# CATZILLA.net
KiCad netlist of a schematic drawn in Altium Designer
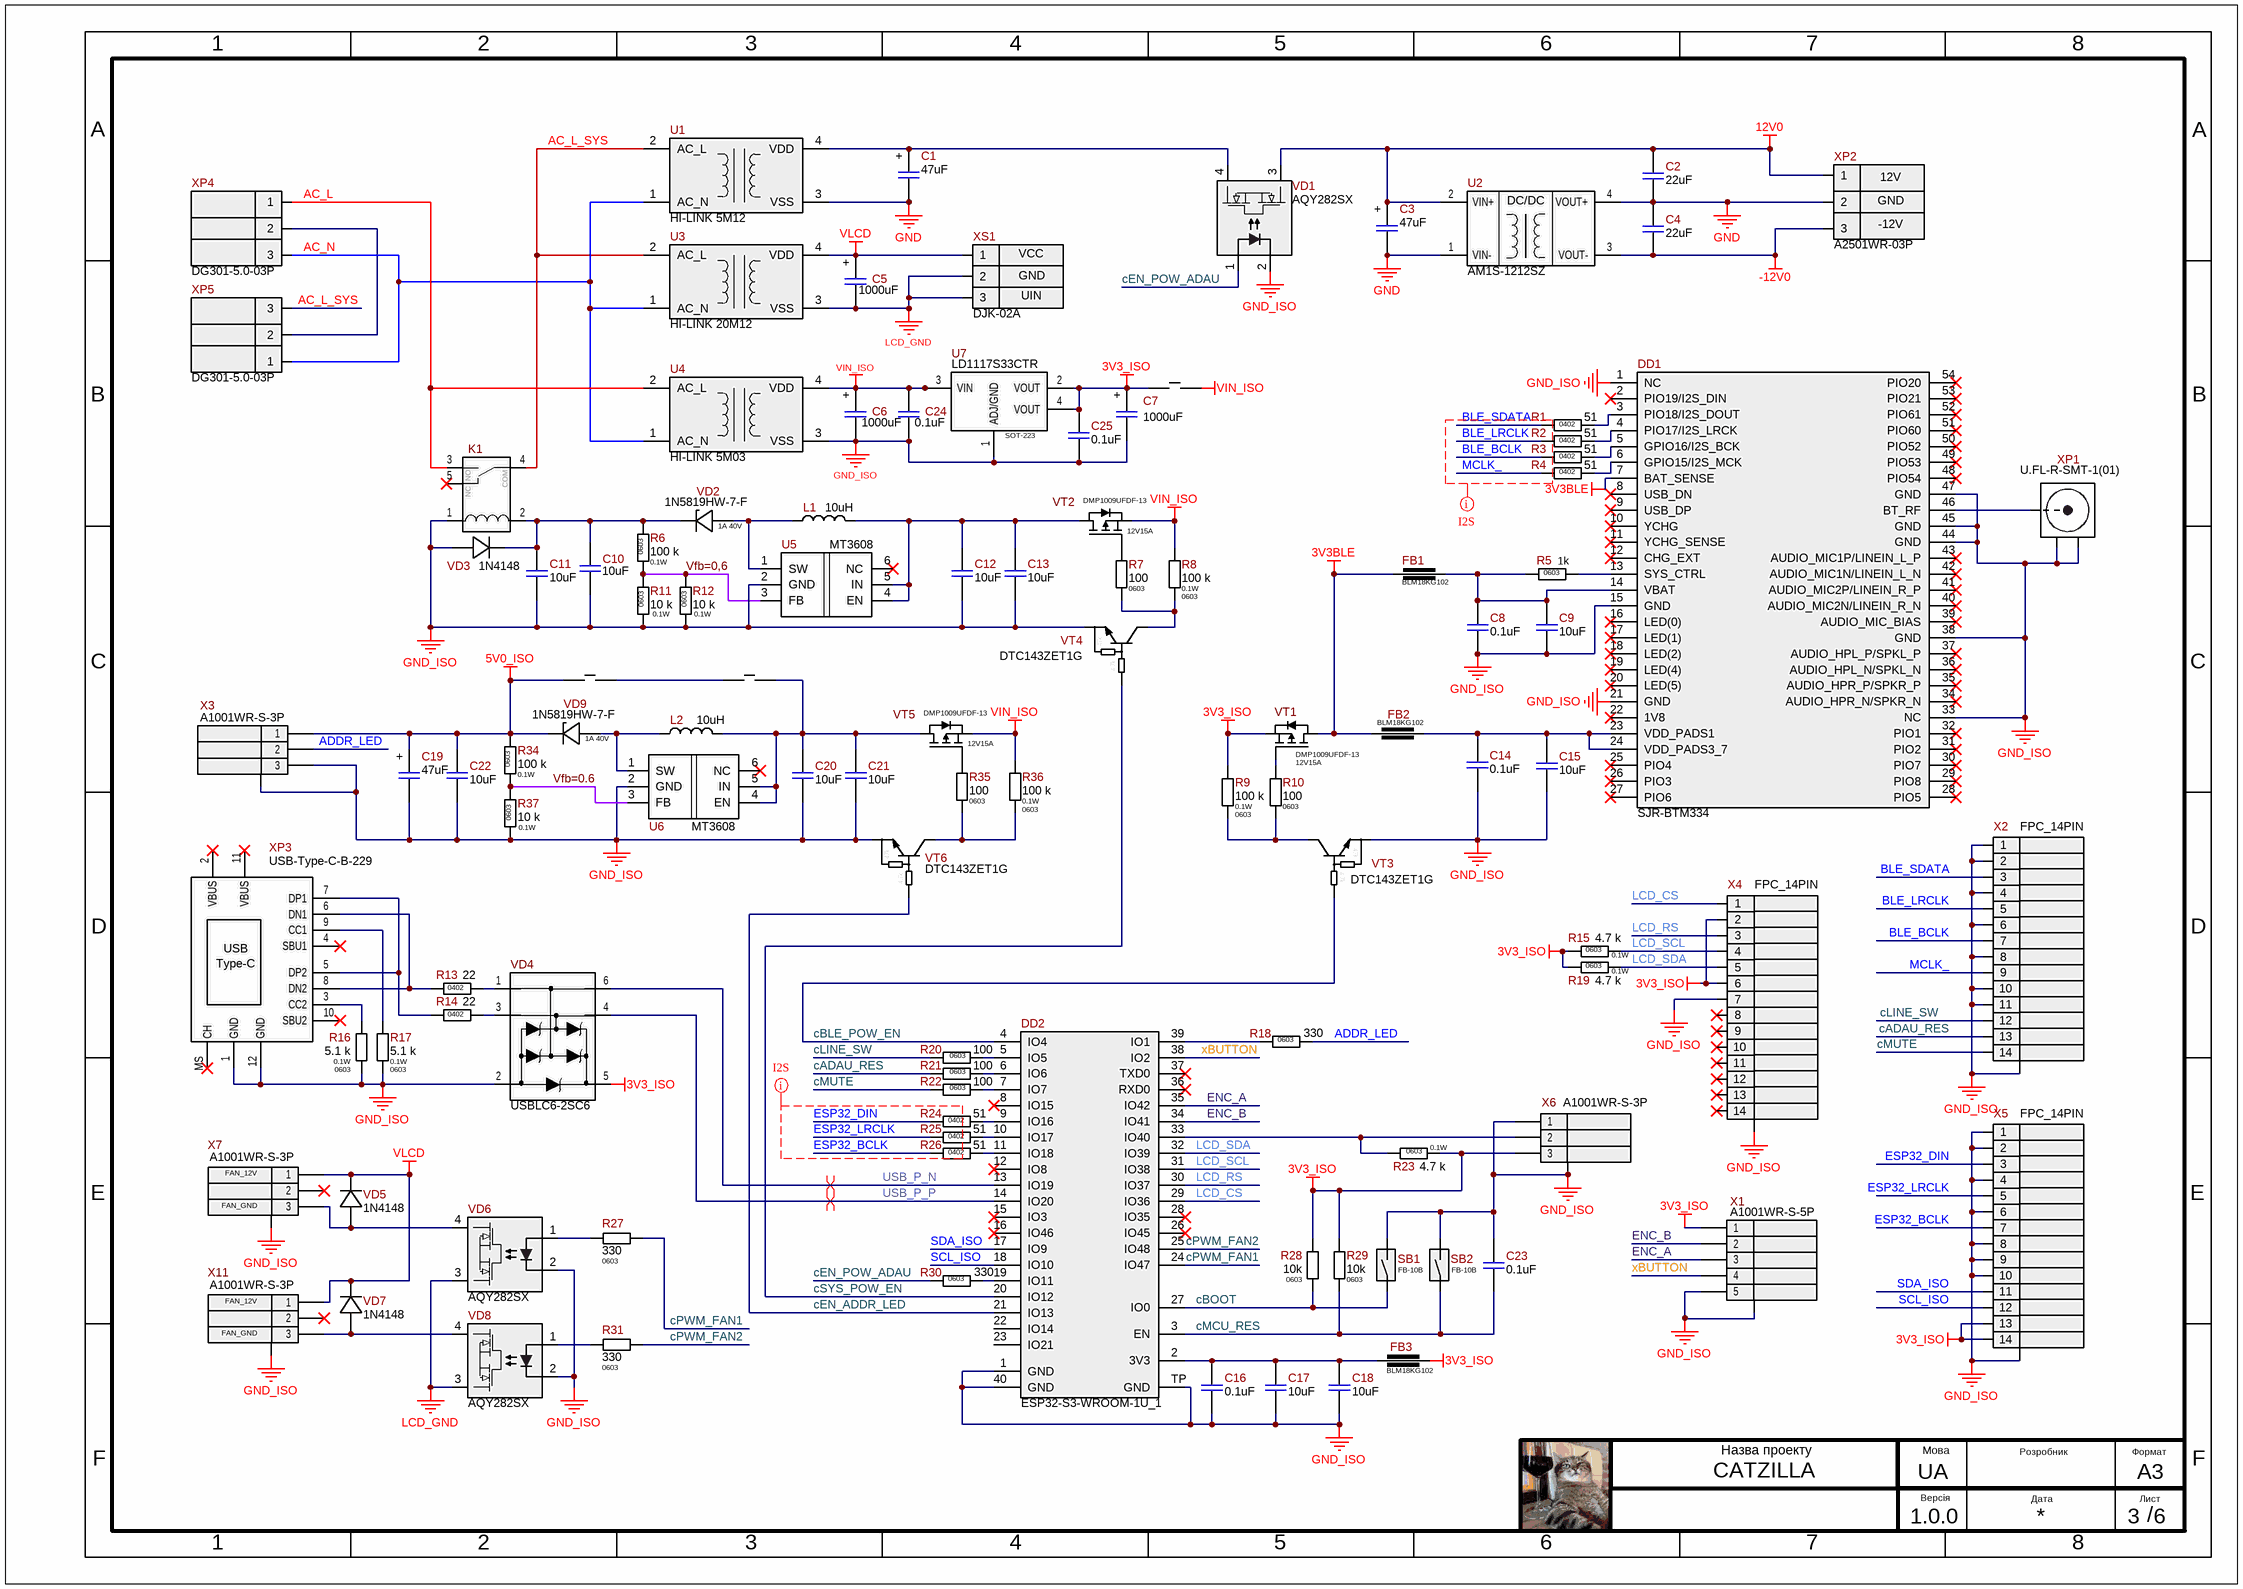
[diagram p0: CATZILLA.SchDoc]

(export (version "E")
  (design (tool "Eeschema 10.0.6"))
  (components
    (comp (ref "C1")
      (value "47uF")
      (footprint "CAP 6.3x6")
      (description "CAP ALUM POLY 47UF 10% 25V SMD")
      (fields (field (name "PART NUMBER") "47uF  25V 6.3х5.3") (field (name "TOLERANCE") "±10%"))
      (libsource (lib "Database") (part "Capacitor_Electrolytic"))
    )
    (comp (ref "C2")
      (value "22uF")
      (footprint "C1206(3216)")
      (description "CAP CER 22UF 25V X5R 1206")
      (fields (field (name "PART NUMBER") "22uF  25V С1206") (field (name "TOLERANCE") "±10%"))
      (libsource (lib "Database") (part "Capacitor_Ceramic"))
    )
    (comp (ref "C3")
      (value "47uF")
      (footprint "CAP 6.3x6")
      (description "CAP ALUM POLY 47UF 10% 25V SMD")
      (fields (field (name "PART NUMBER") "47uF  25V 6.3х5.3") (field (name "TOLERANCE") "±10%"))
      (libsource (lib "Database") (part "Capacitor_Electrolytic"))
    )
    (comp (ref "C4")
      (value "22uF")
      (footprint "C1206(3216)")
      (description "CAP CER 22UF 25V X5R 1206")
      (fields (field (name "PART NUMBER") "22uF  25V С1206") (field (name "TOLERANCE") "±10%"))
      (libsource (lib "Database") (part "Capacitor_Ceramic"))
    )
    (comp (ref "C5")
      (value "1000uF")
      (footprint "CAP 10x16")
      (description "1000uF 20% 16V EHR 10x16mm")
      (fields (field (name "PART NUMBER") "1000uF  16V 10x16(EHR)") (field (name "TOLERANCE") "±20%"))
      (libsource (lib "Database") (part "Capacitor_Electrolytic"))
    )
    (comp (ref "C6")
      (value "1000uF")
      (footprint "CAP-AE-830x1000H50_HI")
      (description "1000uF 6.3V Size E D8x10.5mm")
      (fields (field (name "PART NUMBER") "1000uF  6.3V Size E D8x10.5mm") (field (name "TOLERANCE") "10%"))
      (libsource (lib "Database") (part "Capacitor_Electrolytic"))
    )
    (comp (ref "C7")
      (value "1000uF")
      (footprint "CAP-AE-830x1000H50_HI")
      (description "1000uF 6.3V Size E D8x10.5mm")
      (fields (field (name "PART NUMBER") "1000uF  6.3V Size E D8x10.5mm") (field (name "TOLERANCE") "10%"))
      (libsource (lib "Database") (part "Capacitor_Electrolytic"))
    )
    (comp (ref "C8")
      (value "0.1uF")
      (footprint "C0603(1608)")
      (description "CAP CER 0.1UF 50V X7R 0603")
      (fields (field (name "PART NUMBER") "0.1uF  50V C0603") (field (name "TOLERANCE") "±10%"))
      (libsource (lib "Database") (part "Capacitor_Ceramic"))
    )
    (comp (ref "C9")
      (value "10uF")
      (footprint "C0603(1608)")
      (description "CAP CER 10UF 35V X5R 0603")
      (fields (field (name "PART NUMBER") "10uF  35V C0603") (field (name "TOLERANCE") "±20%"))
      (libsource (lib "Database") (part "Capacitor_Ceramic"))
    )
    (comp (ref "C10")
      (value "10uF")
      (footprint "C0805(2012)")
      (description "CAP CER 10UF 16V X6S 0805")
      (fields (field (name "PART NUMBER") "10uF  16V C0805") (field (name "TOLERANCE") "±10%"))
      (libsource (lib "Database") (part "Capacitor_Ceramic"))
    )
    (comp (ref "C11")
      (value "10uF")
      (footprint "C0805(2012)")
      (description "CAP CER 10UF 16V X6S 0805")
      (fields (field (name "PART NUMBER") "10uF  16V C0805") (field (name "TOLERANCE") "±10%"))
      (libsource (lib "Database") (part "Capacitor_Ceramic"))
    )
    (comp (ref "C12")
      (value "10uF")
      (footprint "C0805(2012)")
      (description "CAP CER 10UF 16V X6S 0805")
      (fields (field (name "PART NUMBER") "10uF  16V C0805") (field (name "TOLERANCE") "±10%"))
      (libsource (lib "Database") (part "Capacitor_Ceramic"))
    )
    (comp (ref "C13")
      (value "10uF")
      (footprint "C0805(2012)")
      (description "CAP CER 10UF 16V X6S 0805")
      (fields (field (name "PART NUMBER") "10uF  16V C0805") (field (name "TOLERANCE") "±10%"))
      (libsource (lib "Database") (part "Capacitor_Ceramic"))
    )
    (comp (ref "C14")
      (value "0.1uF")
      (footprint "C0603(1608)")
      (description "CAP CER 0.1UF 50V X7R 0603")
      (fields (field (name "PART NUMBER") "0.1uF  50V C0603") (field (name "TOLERANCE") "±10%"))
      (libsource (lib "Database") (part "Capacitor_Ceramic"))
    )
    (comp (ref "C15")
      (value "10uF")
      (footprint "C0603(1608)")
      (description "CAP CER 10UF 35V X5R 0603")
      (fields (field (name "PART NUMBER") "10uF  35V C0603") (field (name "TOLERANCE") "±20%"))
      (libsource (lib "Database") (part "Capacitor_Ceramic"))
    )
    (comp (ref "C16")
      (value "0.1uF")
      (footprint "C0603(1608)")
      (description "CAP CER 0.1UF 50V X7R 0603")
      (fields (field (name "PART NUMBER") "0.1uF  50V C0603") (field (name "TOLERANCE") "±10%"))
      (libsource (lib "Database") (part "Capacitor_Ceramic"))
    )
    (comp (ref "C17")
      (value "10uF")
      (footprint "C0603(1608)")
      (description "CAP CER 10UF 35V X5R 0603")
      (fields (field (name "PART NUMBER") "10uF  35V C0603") (field (name "TOLERANCE") "±20%"))
      (libsource (lib "Database") (part "Capacitor_Ceramic"))
    )
    (comp (ref "C18")
      (value "10uF")
      (footprint "C0603(1608)")
      (description "CAP CER 10UF 35V X5R 0603")
      (fields (field (name "PART NUMBER") "10uF  35V C0603") (field (name "TOLERANCE") "±20%"))
      (libsource (lib "Database") (part "Capacitor_Ceramic"))
    )
    (comp (ref "C19")
      (value "47uF")
      (footprint "CAP 6.3x6")
      (description "CAP ALUM POLY 47UF 10% 25V SMD")
      (fields (field (name "PART NUMBER") "47uF  25V 6.3х5.3") (field (name "TOLERANCE") "±10%"))
      (libsource (lib "Database") (part "Capacitor_Electrolytic"))
    )
    (comp (ref "C20")
      (value "10uF")
      (footprint "C0805(2012)")
      (description "CAP CER 10UF 16V X6S 0805")
      (fields (field (name "PART NUMBER") "10uF  16V C0805") (field (name "TOLERANCE") "±10%"))
      (libsource (lib "Database") (part "Capacitor_Ceramic"))
    )
    (comp (ref "C21")
      (value "10uF")
      (footprint "C0805(2012)")
      (description "CAP CER 10UF 16V X6S 0805")
      (fields (field (name "PART NUMBER") "10uF  16V C0805") (field (name "TOLERANCE") "±10%"))
      (libsource (lib "Database") (part "Capacitor_Ceramic"))
    )
    (comp (ref "C22")
      (value "10uF")
      (footprint "C0805(2012)")
      (description "CAP CER 10UF 16V X6S 0805")
      (fields (field (name "PART NUMBER") "10uF  16V C0805") (field (name "TOLERANCE") "±10%"))
      (libsource (lib "Database") (part "Capacitor_Ceramic"))
    )
    (comp (ref "C23")
      (value "0.1uF")
      (footprint "C0603(1608)")
      (description "CAP CER 0.1UF 50V X7R 0603")
      (fields (field (name "PART NUMBER") "0.1uF  50V C0603") (field (name "TOLERANCE") "±10%"))
      (libsource (lib "Database") (part "Capacitor_Ceramic"))
    )
    (comp (ref "C24")
      (value "0.1uF")
      (footprint "C0603(1608)")
      (description "CAP CER 0.1UF 50V X7R 0603")
      (fields (field (name "PART NUMBER") "0.1uF  50V C0603") (field (name "TOLERANCE") "±10%"))
      (libsource (lib "Database") (part "Capacitor_Ceramic"))
    )
    (comp (ref "C25")
      (value "0.1uF")
      (footprint "C0603(1608)")
      (description "CAP CER 0.1UF 50V X7R 0603")
      (fields (field (name "PART NUMBER") "0.1uF  50V C0603") (field (name "TOLERANCE") "±10%"))
      (libsource (lib "Database") (part "Capacitor_Ceramic"))
    )
    (comp (ref "DD1")
      (value "SJR-BTM334")
      (footprint "BTM334")
      (description "Bluetooth 5.1 audio module, QCC3034 chipset")
      (libsource (lib "Database") (part "BTM334"))
    )
    (comp (ref "DD2")
      (value "ESP32-S3-WROOM-1U_1")
      (footprint "ESP32-S3-WROOM-1U")
      (description "ESP32-S3-WROOM-1U-N16R8")
      (libsource (lib "Database") (part "ESP32-S3-WROOM-1U-1N16R2"))
    )
    (comp (ref "FB1")
      (value "BLM18KG102")
      (footprint "BLM18(0603)")
      (description "FERRITE BEAD 1 KOHM 0603 1LN")
      (fields
        (field (name "TOLERANCE") "±25%")
        (field (name "MANUFACTURER") "Murata Electronics North America")
      )
      (libsource (lib "Database") (part "FB"))
    )
    (comp (ref "FB2")
      (value "BLM18KG102")
      (footprint "BLM18(0603)")
      (description "FERRITE BEAD 1 KOHM 0603 1LN")
      (fields
        (field (name "TOLERANCE") "±25%")
        (field (name "MANUFACTURER") "Murata Electronics North America")
      )
      (libsource (lib "Database") (part "FB"))
    )
    (comp (ref "FB3")
      (value "BLM18KG102")
      (footprint "BLM18(0603)")
      (description "FERRITE BEAD 1 KOHM 0603 1LN")
      (fields
        (field (name "TOLERANCE") "±25%")
        (field (name "MANUFACTURER") "Murata Electronics North America")
      )
      (libsource (lib "Database") (part "FB"))
    )
    (comp (ref "K1")
      (value "LEG-12")
      (footprint "Relay10A")
      (description "General Purpose Relay, 1 Form C (1PDT), 12VDC 400Ohm Coil, 120VAC/24VDC @ 10A, 240VAC Max")
      (libsource (lib "Database") (part "RELAY10A"))
    )
    (comp (ref "L1")
      (value "10uH")
      (footprint "WE-LQS SMD 4018")
      (description "FIXED IND 10UH 1A 66 MOHM SMD")
      (fields (field (name "PART NUMBER") "NRS4018T3R3") (field (name "TOLERANCE") "±20"))
      (libsource (lib "Database") (part "INDUCTORS"))
    )
    (comp (ref "L2")
      (value "10uH")
      (footprint "WE-LQS SMD 4018")
      (description "FIXED IND 10UH 1A 66 MOHM SMD")
      (fields (field (name "PART NUMBER") "NRS4018T3R3") (field (name "TOLERANCE") "±20"))
      (libsource (lib "Database") (part "INDUCTORS"))
    )
    (comp (ref "R1")
      (value "51")
      (footprint "R0402")
      (description "RES SMD 51 OHM  ±1% 1/16W 0402")
      (fields
        (field (name "PACKAGE/CASE") "0402")
        (field (name "PART NUMBER") "51  R0402")
        (field (name "TOLERANCE") "±1%")
      )
      (libsource (lib "Database") (part "R0402"))
    )
    (comp (ref "R2")
      (value "51")
      (footprint "R0402")
      (description "RES SMD 51 OHM  ±1% 1/16W 0402")
      (fields
        (field (name "PACKAGE/CASE") "0402")
        (field (name "PART NUMBER") "51  R0402")
        (field (name "TOLERANCE") "±1%")
      )
      (libsource (lib "Database") (part "R0402"))
    )
    (comp (ref "R3")
      (value "51")
      (footprint "R0402")
      (description "RES SMD 51 OHM  ±1% 1/16W 0402")
      (fields
        (field (name "PACKAGE/CASE") "0402")
        (field (name "PART NUMBER") "51  R0402")
        (field (name "TOLERANCE") "±1%")
      )
      (libsource (lib "Database") (part "R0402"))
    )
    (comp (ref "R4")
      (value "51")
      (footprint "R0402")
      (description "RES SMD 51 OHM  ±1% 1/16W 0402")
      (fields
        (field (name "PACKAGE/CASE") "0402")
        (field (name "PART NUMBER") "51  R0402")
        (field (name "TOLERANCE") "±1%")
      )
      (libsource (lib "Database") (part "R0402"))
    )
    (comp (ref "R5")
      (value "1k")
      (footprint "R0603")
      (description "RES SMD 10 k OHM  ±1% 1/10W 0603")
      (fields
        (field (name "PACKAGE/CASE") "0603")
        (field (name "PART NUMBER") "10 k  R0603")
        (field (name "TOLERANCE") "±1%")
      )
      (libsource (lib "Database") (part "R0603"))
    )
    (comp (ref "R6")
      (value "100 k")
      (footprint "R0603")
      (description "RES SMD 100 k OHM  ±1% 1/10W 0603")
      (fields
        (field (name "POWER RATING") "0.1W")
        (field (name "PACKAGE/CASE") "0603")
        (field (name "PART NUMBER") "100 k  R0603")
        (field (name "TOLERANCE") "±1%")
      )
      (libsource (lib "Database") (part "R0603"))
    )
    (comp (ref "R7")
      (value "100")
      (footprint "R0603")
      (description "RES SMD 100 OHM  ±1% 1/10W 0603")
      (fields
        (field (name "PACKAGE/CASE") "0603")
        (field (name "PART NUMBER") "100  R0603")
        (field (name "TOLERANCE") "±1%")
      )
      (libsource (lib "Database") (part "R0603"))
    )
    (comp (ref "R8")
      (value "100 k")
      (footprint "R0603")
      (description "RES SMD 100 k OHM  ±1% 1/10W 0603")
      (fields
        (field (name "POWER RATING") "0.1W")
        (field (name "PACKAGE/CASE") "0603")
        (field (name "PART NUMBER") "100 k  R0603")
        (field (name "TOLERANCE") "±1%")
      )
      (libsource (lib "Database") (part "R0603"))
    )
    (comp (ref "R9")
      (value "100 k")
      (footprint "R0603")
      (description "RES SMD 100 k OHM  ±1% 1/10W 0603")
      (fields
        (field (name "POWER RATING") "0.1W")
        (field (name "PACKAGE/CASE") "0603")
        (field (name "PART NUMBER") "100 k  R0603")
        (field (name "TOLERANCE") "±1%")
      )
      (libsource (lib "Database") (part "R0603"))
    )
    (comp (ref "R10")
      (value "100")
      (footprint "R0603")
      (description "RES SMD 100 OHM  ±1% 1/10W 0603")
      (fields
        (field (name "PACKAGE/CASE") "0603")
        (field (name "PART NUMBER") "100  R0603")
        (field (name "TOLERANCE") "±1%")
      )
      (libsource (lib "Database") (part "R0603"))
    )
    (comp (ref "R11")
      (value "10 k")
      (footprint "R0603")
      (description "RES SMD 10 k OHM  ±1% 1/10W 0603")
      (fields
        (field (name "PACKAGE/CASE") "0603")
        (field (name "POWER RATING") "0.1W")
        (field (name "PART NUMBER") "10 k  R0603")
        (field (name "TOLERANCE") "±1%")
      )
      (libsource (lib "Database") (part "R0603"))
    )
    (comp (ref "R12")
      (value "10 k")
      (footprint "R0603")
      (description "RES SMD 10 k OHM  ±1% 1/10W 0603")
      (fields
        (field (name "PACKAGE/CASE") "0603")
        (field (name "POWER RATING") "0.1W")
        (field (name "PART NUMBER") "10 k  R0603")
        (field (name "TOLERANCE") "±1%")
      )
      (libsource (lib "Database") (part "R0603"))
    )
    (comp (ref "R13")
      (value "22")
      (footprint "R0402")
      (description "RES SMD 22 OHM  ±1% 1/16W 0402")
      (fields
        (field (name "PACKAGE/CASE") "0402")
        (field (name "PART NUMBER") "22  R0402")
        (field (name "TOLERANCE") "±1%")
      )
      (libsource (lib "Database") (part "R0402"))
    )
    (comp (ref "R14")
      (value "22")
      (footprint "R0402")
      (description "RES SMD 22 OHM  ±1% 1/16W 0402")
      (fields
        (field (name "PACKAGE/CASE") "0402")
        (field (name "PART NUMBER") "22  R0402")
        (field (name "TOLERANCE") "±1%")
      )
      (libsource (lib "Database") (part "R0402"))
    )
    (comp (ref "R15")
      (value "4.7 k")
      (footprint "R0603")
      (description "RES SMD 4.7 k OHM  ±1% 1/10W 0603")
      (fields
        (field (name "POWER RATING") "0.1W")
        (field (name "PACKAGE/CASE") "0603")
        (field (name "PART NUMBER") "4.7 k  R0603")
        (field (name "TOLERANCE") "±1%")
      )
      (libsource (lib "Database") (part "R0603"))
    )
    (comp (ref "R16")
      (value "5.1 k")
      (footprint "R0603")
      (description "RES SMD 5.1 k OHM  ±1% 1/10W 0603")
      (fields
        (field (name "POWER RATING") "0.1W")
        (field (name "PACKAGE/CASE") "0603")
        (field (name "PART NUMBER") "5.1 k  R0603")
        (field (name "TOLERANCE") "±1%")
      )
      (libsource (lib "Database") (part "R0603"))
    )
    (comp (ref "R17")
      (value "5.1 k")
      (footprint "R0603")
      (description "RES SMD 5.1 k OHM  ±1% 1/10W 0603")
      (fields
        (field (name "POWER RATING") "0.1W")
        (field (name "PACKAGE/CASE") "0603")
        (field (name "PART NUMBER") "5.1 k  R0603")
        (field (name "TOLERANCE") "±1%")
      )
      (libsource (lib "Database") (part "R0603"))
    )
    (comp (ref "R18")
      (value "330")
      (footprint "R0603")
      (description "RES SMD 330 OHM  ±1% 1/10W 0603")
      (fields
        (field (name "PACKAGE/CASE") "0603")
        (field (name "PART NUMBER") "330  R0603")
        (field (name "TOLERANCE") "±1%")
      )
      (libsource (lib "Database") (part "R0603"))
    )
    (comp (ref "R19")
      (value "4.7 k")
      (footprint "R0603")
      (description "RES SMD 4.7 k OHM  ±1% 1/10W 0603")
      (fields
        (field (name "POWER RATING") "0.1W")
        (field (name "PACKAGE/CASE") "0603")
        (field (name "PART NUMBER") "4.7 k  R0603")
        (field (name "TOLERANCE") "±1%")
      )
      (libsource (lib "Database") (part "R0603"))
    )
    (comp (ref "R20")
      (value "100")
      (footprint "R0603")
      (description "RES SMD 100 OHM  ±1% 1/10W 0603")
      (fields
        (field (name "PACKAGE/CASE") "0603")
        (field (name "PART NUMBER") "100  R0603")
        (field (name "TOLERANCE") "±1%")
      )
      (libsource (lib "Database") (part "R0603"))
    )
    (comp (ref "R21")
      (value "100")
      (footprint "R0603")
      (description "RES SMD 100 OHM  ±1% 1/10W 0603")
      (fields
        (field (name "PACKAGE/CASE") "0603")
        (field (name "PART NUMBER") "100  R0603")
        (field (name "TOLERANCE") "±1%")
      )
      (libsource (lib "Database") (part "R0603"))
    )
    (comp (ref "R22")
      (value "100")
      (footprint "R0603")
      (description "RES SMD 100 OHM  ±1% 1/10W 0603")
      (fields
        (field (name "PACKAGE/CASE") "0603")
        (field (name "PART NUMBER") "100  R0603")
        (field (name "TOLERANCE") "±1%")
      )
      (libsource (lib "Database") (part "R0603"))
    )
    (comp (ref "R23")
      (value "4.7 k")
      (footprint "R0603")
      (description "RES SMD 4.7 k OHM  ±1% 1/10W 0603")
      (fields
        (field (name "POWER RATING") "0.1W")
        (field (name "PACKAGE/CASE") "0603")
        (field (name "PART NUMBER") "4.7 k  R0603")
        (field (name "TOLERANCE") "±1%")
      )
      (libsource (lib "Database") (part "R0603"))
    )
    (comp (ref "R24")
      (value "51")
      (footprint "R0402")
      (description "RES SMD 51 OHM  ±1% 1/16W 0402")
      (fields
        (field (name "PACKAGE/CASE") "0402")
        (field (name "PART NUMBER") "51  R0402")
        (field (name "TOLERANCE") "±1%")
      )
      (libsource (lib "Database") (part "R0402"))
    )
    (comp (ref "R25")
      (value "51")
      (footprint "R0402")
      (description "RES SMD 51 OHM  ±1% 1/16W 0402")
      (fields
        (field (name "PACKAGE/CASE") "0402")
        (field (name "PART NUMBER") "51  R0402")
        (field (name "TOLERANCE") "±1%")
      )
      (libsource (lib "Database") (part "R0402"))
    )
    (comp (ref "R26")
      (value "51")
      (footprint "R0402")
      (description "RES SMD 51 OHM  ±1% 1/16W 0402")
      (fields
        (field (name "PACKAGE/CASE") "0402")
        (field (name "PART NUMBER") "51  R0402")
        (field (name "TOLERANCE") "±1%")
      )
      (libsource (lib "Database") (part "R0402"))
    )
    (comp (ref "R27")
      (value "330")
      (footprint "R0603")
      (description "RES SMD 330 OHM  ±1% 1/10W 0603")
      (fields
        (field (name "PACKAGE/CASE") "0603")
        (field (name "PART NUMBER") "330  R0603")
        (field (name "TOLERANCE") "±1%")
      )
      (libsource (lib "Database") (part "R0603"))
    )
    (comp (ref "R28")
      (value "10k")
      (footprint "R0603")
      (description "RES SMD 10 k OHM  ±1% 1/10W 0603")
      (fields
        (field (name "PACKAGE/CASE") "0603")
        (field (name "PART NUMBER") "10 k  R0603")
        (field (name "TOLERANCE") "±1%")
      )
      (libsource (lib "Database") (part "R0603"))
    )
    (comp (ref "R29")
      (value "10k")
      (footprint "R0603")
      (description "RES SMD 10 k OHM  ±1% 1/10W 0603")
      (fields
        (field (name "PACKAGE/CASE") "0603")
        (field (name "PART NUMBER") "10 k  R0603")
        (field (name "TOLERANCE") "±1%")
      )
      (libsource (lib "Database") (part "R0603"))
    )
    (comp (ref "R30")
      (value "330")
      (footprint "R0603")
      (description "RES SMD 330 OHM  ±1% 1/10W 0603")
      (fields
        (field (name "PACKAGE/CASE") "0603")
        (field (name "PART NUMBER") "330  R0603")
        (field (name "TOLERANCE") "±1%")
      )
      (libsource (lib "Database") (part "R0603"))
    )
    (comp (ref "R31")
      (value "330")
      (footprint "R0603")
      (description "RES SMD 330 OHM  ±1% 1/10W 0603")
      (fields
        (field (name "PACKAGE/CASE") "0603")
        (field (name "PART NUMBER") "330  R0603")
        (field (name "TOLERANCE") "±1%")
      )
      (libsource (lib "Database") (part "R0603"))
    )
    (comp (ref "R34")
      (value "100 k")
      (footprint "R0603")
      (description "RES SMD 100 k OHM  ±1% 1/10W 0603")
      (fields
        (field (name "POWER RATING") "0.1W")
        (field (name "PACKAGE/CASE") "0603")
        (field (name "PART NUMBER") "100 k  R0603")
        (field (name "TOLERANCE") "±1%")
      )
      (libsource (lib "Database") (part "R0603"))
    )
    (comp (ref "R35")
      (value "100")
      (footprint "R0603")
      (description "RES SMD 100 OHM  ±1% 1/10W 0603")
      (fields
        (field (name "PACKAGE/CASE") "0603")
        (field (name "PART NUMBER") "100  R0603")
        (field (name "TOLERANCE") "±1%")
      )
      (libsource (lib "Database") (part "R0603"))
    )
    (comp (ref "R36")
      (value "100 k")
      (footprint "R0603")
      (description "RES SMD 100 k OHM  ±1% 1/10W 0603")
      (fields
        (field (name "POWER RATING") "0.1W")
        (field (name "PACKAGE/CASE") "0603")
        (field (name "PART NUMBER") "100 k  R0603")
        (field (name "TOLERANCE") "±1%")
      )
      (libsource (lib "Database") (part "R0603"))
    )
    (comp (ref "R37")
      (value "10 k")
      (footprint "R0603")
      (description "RES SMD 10 k OHM  ±1% 1/10W 0603")
      (fields
        (field (name "PACKAGE/CASE") "0603")
        (field (name "POWER RATING") "0.1W")
        (field (name "PART NUMBER") "10 k  R0603")
        (field (name "TOLERANCE") "±1%")
      )
      (libsource (lib "Database") (part "R0603"))
    )
    (comp (ref "SB1") (value "FB-10B") (footprint "FB-10B") (libsource (lib "Database") (part "Button")))
    (comp (ref "SB2") (value "FB-10B") (footprint "FB-10B") (libsource (lib "Database") (part "Button")))
    (comp (ref "U1")
      (value "HI-LINK 5M12")
      (footprint "HLINK_5MXX")
      (description "85-264VAC  5W 12V 0.45A")
      (libsource (lib "Database") (part "HI-LINK XXMXX"))
    )
    (comp (ref "U2")
      (value "AM1S-1212SZ")
      (footprint "SIP-4")
      (description "Isolated Module DC DC Converter, 1 Output 12V 83mA, 10.8V - 13.2V Input")
      (libsource (lib "Database") (part "AM1S-1212SZ"))
    )
    (comp (ref "U3")
      (value "HI-LINK 20M12")
      (footprint "HLINK_20MXX")
      (description "85-264VAC  20W 12V 1.6A")
      (libsource (lib "Database") (part "HI-LINK XXMXX"))
    )
    (comp (ref "U4")
      (value "HI-LINK 5M03")
      (footprint "HLINK_5MXX")
      (description "85-264VAC  5W 3.3V 1.5A")
      (libsource (lib "Database") (part "HI-LINK XXMXX"))
    )
    (comp (ref "U5")
      (value "MT3608")
      (footprint "SOT23-6")
      (description "HIGH EFFICIENCY 1.2MHZ 2A STEP UP CONVERTER")
      (fields (field (name "MANUFACTURER") "AEROSEMI"))
      (libsource (lib "Database") (part "MT3608"))
    )
    (comp (ref "U6")
      (value "MT3608")
      (footprint "SOT23-6")
      (description "HIGH EFFICIENCY 1.2MHZ 2A STEP UP CONVERTER")
      (fields (field (name "MANUFACTURER") "AEROSEMI"))
      (libsource (lib "Database") (part "MT3608"))
    )
    (comp (ref "U7")
      (value "LD1117STR")
      (footprint "SOT223")
      (description "IC REG LINEAR 3.3V 800MA SOT223")
      (fields
        (field (name "MANUFACTURER") "STMicroelectronics")
        (field (name "PACKAGE") "SOT-223")
        (field (name "PART NUMBER") "LD1117S33CTR")
      )
      (libsource (lib "Database") (part "LD1117S"))
    )
    (comp (ref "VD1")
      (value "AQY282SX")
      (footprint "SOP-4N")
      (description "SSR RELAY SPST-NO 500MA 0-60V")
      (fields (field (name "MANUFACTURER") "Panasonic Electric Works"))
      (libsource (lib "") (part "AQY282SX_1"))
    )
    (comp (ref "VD2")
      (value "1N5819HW-7-F")
      (footprint "SOD-123")
      (description "DIODE SCHOTTKY 40V 1A SOD-123")
      (fields (field (name "POWER RATING") "1A 40V") (field (name "MANUFACTURER") "Diodes Incorporated"))
      (libsource (lib "Database") (part "SCHOTTKY"))
    )
    (comp (ref "VD3")
      (value "1N4148")
      (footprint "SOD-80")
      (description "DIODE GEN PURP 75V 250MA SOD323")
      (fields (field (name "MANUFACTURER") "Diodes Incorporated"))
      (libsource (lib "Database") (part "DIODE"))
    )
    (comp (ref "VD4")
      (value "USBLC6-2SC6")
      (footprint "SOT-666")
      (description "TVS DIODE 5.25V 17V SOT23-6")
      (fields (field (name "MANUFACTURER") "STMicroelectronics"))
      (libsource (lib "Database") (part "USBLC6-2"))
    )
    (comp (ref "VD5")
      (value "1N4148")
      (footprint "D0805")
      (description "DIODE GEN PURP 75V 250MA SOD323")
      (fields (field (name "MANUFACTURER") "Diodes Incorporated"))
      (libsource (lib "Database") (part "DIODE"))
    )
    (comp (ref "VD6")
      (value "AQY282SX")
      (footprint "SOP-4N")
      (description "SSR RELAY SPST-NO 500MA 0-60V")
      (fields (field (name "MANUFACTURER") "Panasonic Electric Works"))
      (libsource (lib "Database") (part "AQY282SX"))
    )
    (comp (ref "VD7")
      (value "1N4148")
      (footprint "D0805")
      (description "DIODE GEN PURP 75V 250MA SOD323")
      (fields (field (name "MANUFACTURER") "Diodes Incorporated"))
      (libsource (lib "Database") (part "DIODE"))
    )
    (comp (ref "VD8")
      (value "AQY282SX")
      (footprint "SOP-4N")
      (description "SSR RELAY SPST-NO 500MA 0-60V")
      (fields (field (name "MANUFACTURER") "Panasonic Electric Works"))
      (libsource (lib "Database") (part "AQY282SX"))
    )
    (comp (ref "VD9")
      (value "1N5819HW-7-F")
      (footprint "SOD-123")
      (description "DIODE SCHOTTKY 40V 1A SOD-123")
      (fields (field (name "POWER RATING") "1A 40V") (field (name "MANUFACTURER") "Diodes Incorporated"))
      (libsource (lib "Database") (part "SCHOTTKY"))
    )
    (comp (ref "VT1")
      (value "DMP1009UFDF-13")
      (footprint "U-DFN2020-6_SLDR")
      (description "P-Channel 12 V 15A (Ta) 2W (Ta) Surface Mount U-DFN2020-6 (Type F)")
      (fields (field (name "POWER RATING") "12V15A") (field (name "MANUFACTURER") "Diodes Incorporated"))
      (libsource (lib "Database") (part "DMP1009UFDF"))
    )
    (comp (ref "VT2")
      (value "DMP1009UFDF-13")
      (footprint "U-DFN2020-6_SLDR")
      (description "P-Channel 12 V 15A (Ta) 2W (Ta) Surface Mount U-DFN2020-6 (Type F)")
      (fields (field (name "POWER RATING") "12V15A") (field (name "MANUFACTURER") "Diodes Incorporated"))
      (libsource (lib "Database") (part "DMP1009UFDF"))
    )
    (comp (ref "VT3")
      (value "DTC143ZET1G")
      (footprint "SOT-416")
      (description "TRANS PREBIAS NPN 50V 100MA SC75")
      (fields (field (name "MANUFACTURER") "onsemi"))
      (libsource (lib "Database") (part "Bipolar_NPN_Pre-Biased"))
    )
    (comp (ref "VT4")
      (value "DTC143ZET1G")
      (footprint "SOT-416")
      (description "TRANS PREBIAS NPN 50V 100MA SC75")
      (fields (field (name "MANUFACTURER") "onsemi"))
      (libsource (lib "Database") (part "Bipolar_NPN_Pre-Biased"))
    )
    (comp (ref "VT5")
      (value "DMP1009UFDF-13")
      (footprint "U-DFN2020-6_SLDR")
      (description "P-Channel 12 V 15A (Ta) 2W (Ta) Surface Mount U-DFN2020-6 (Type F)")
      (fields (field (name "POWER RATING") "12V15A") (field (name "MANUFACTURER") "Diodes Incorporated"))
      (libsource (lib "Database") (part "DMP1009UFDF"))
    )
    (comp (ref "VT6")
      (value "DTC143ZET1G")
      (footprint "SOT-416")
      (description "TRANS PREBIAS NPN 50V 100MA SC75")
      (fields (field (name "MANUFACTURER") "onsemi"))
      (libsource (lib "Database") (part "Bipolar_NPN_Pre-Biased"))
    )
    (comp (ref "X1")
      (value "A1001WR-S-5P")
      (footprint "A1001WR-S-05P")
      (description "CONN HEADER 5POS 1MM")
      (fields (field (name "MANUFACTURER") "Joint Tech"))
      (libsource (lib "Database") (part "A1001WR-S-05P"))
    )
    (comp (ref "X2")
      (value "FPC_14PIN")
      (footprint "FPC-14-0.5mm")
      (description "FPC CONNECTOR")
      (libsource (lib "Database") (part "CON_14_MP"))
    )
    (comp (ref "X3")
      (value "A1001WR-S-3P")
      (footprint "A1001WR-S-03P")
      (description "CONN HEADER 3POS 1MM")
      (fields (field (name "MANUFACTURER") "Joint Tech"))
      (libsource (lib "") (part "A1001WR-S-03P_1"))
    )
    (comp (ref "X4")
      (value "FPC_14PIN")
      (footprint "FPC-14-0.5mm")
      (description "FPC CONNECTOR")
      (libsource (lib "Database") (part "CON_14_MP"))
    )
    (comp (ref "X5")
      (value "FPC_14PIN")
      (footprint "FPC-14-0.5mm")
      (description "FPC CONNECTOR")
      (libsource (lib "Database") (part "CON_14_MP"))
    )
    (comp (ref "X6")
      (value "A1001WR-S-3P")
      (footprint "A1001WR-S-03P")
      (description "CONN HEADER 3POS 1MM")
      (fields (field (name "MANUFACTURER") "Joint Tech"))
      (libsource (lib "Database") (part "A1001WR-S-03P"))
    )
    (comp (ref "X7")
      (value "A1001WR-S-3P")
      (footprint "A1001WR-S-03P")
      (description "CONN HEADER 3POS 1MM")
      (fields (field (name "MANUFACTURER") "Joint Tech"))
      (libsource (lib "") (part "A1001WR-S-03P_1"))
    )
    (comp (ref "X8")
      (value "Jumper 1.5х2")
      (footprint "NetTie1.5х2")
      (description "Jumper 1.5mm x 2mm")
      (libsource (lib "Database") (part "NetTie"))
    )
    (comp (ref "X9")
      (value "Jumper 1.5х2")
      (footprint "NetTie1.5х2")
      (description "Jumper 1.5mm x 2mm")
      (libsource (lib "Database") (part "NetTie"))
    )
    (comp (ref "X10")
      (value "Jumper 1.5х2")
      (footprint "NetTie1.5х2")
      (description "Jumper 1.5mm x 2mm")
      (libsource (lib "Database") (part "NetTie"))
    )
    (comp (ref "X11")
      (value "A1001WR-S-3P")
      (footprint "A1001WR-S-03P")
      (description "CONN HEADER 3POS 1MM")
      (fields (field (name "MANUFACTURER") "Joint Tech"))
      (libsource (lib "") (part "A1001WR-S-03P_1"))
    )
    (comp (ref "XP1")
      (value "U.FL-R-SMT-1(01)")
      (footprint "IPEX_ RECE.20279.001E.01")
      (description "CONN UMC RCPT STR 50 OHM SMD")
      (fields (field (name "MANUFACTURER") "HIROSE"))
      (libsource (lib "Database") (part "IPEX"))
    )
    (comp (ref "XP2")
      (value "A2501WR-03P")
      (footprint "A2501WR-03P")
      (description "PIN: 3; A2501; 3A; 250V; UL94V-0")
      (fields (field (name "MANUFACTURER") "JOINT TECH"))
      (libsource (lib "Database") (part "CON_3"))
    )
    (comp (ref "XP3")
      (value "USB-Type-C-B-229")
      (footprint "USB-Type-C-B-229")
      (fields (field (name "MANUFACTURER") "KLS ELECTRONIC CO., LTD."))
      (libsource (lib "Database") (part "USB-Type-C-B-229"))
    )
    (comp (ref "XP4")
      (value "DG301-5.0-03P")
      (footprint "DG301-5.0-03P")
      (libsource (lib "") (part "CON_3_2"))
    )
    (comp (ref "XP5")
      (value "DG301-5.0-03P")
      (footprint "DG301-5.0-03P")
      (libsource (lib "") (part "CON_3_1"))
    )
    (comp (ref "XS1")
      (value "DJK-02A")
      (footprint "DC-140-003")
      (description "DC POWER JACK CONNECTOR 6.3MM")
      (fields (field (name "MANUFACTURER") "KLS"))
      (libsource (lib "Database") (part "DJK-02A"))
    )
  )
  (nets
    (net (code "1") (name "-12V0") (class "Default")
      (node (ref "C4") (pin "1") (pinfunction "1_1") (pintype "passive"))
      (node (ref "U2") (pin "3") (pinfunction "VOUT-_3") (pintype "passive"))
      (node (ref "XP2") (pin "3") (pinfunction "3_3") (pintype "passive"))
    )
    (net (code "2") (name "/AC_L") (class "Default")
      (node (ref "K1") (pin "3") (pinfunction "NO_3") (pintype "passive"))
      (node (ref "U4") (pin "2") (pinfunction "AC_L_2") (pintype "passive"))
      (node (ref "XP4") (pin "1") (pinfunction "1_1") (pintype "passive"))
    )
    (net (code "3") (name "/AC_L_SYS") (class "Default")
      (node (ref "K1") (pin "4") (pinfunction "COM_4") (pintype "passive"))
      (node (ref "U1") (pin "2") (pinfunction "AC_L_2") (pintype "passive"))
      (node (ref "U3") (pin "2") (pinfunction "AC_L_2") (pintype "passive"))
      (node (ref "XP5") (pin "3") (pinfunction "3_3") (pintype "passive"))
    )
    (net (code "4") (name "/AC_N") (class "Default")
      (node (ref "U1") (pin "1") (pinfunction "AC_N_1") (pintype "passive"))
      (node (ref "U3") (pin "1") (pinfunction "AC_N_1") (pintype "passive"))
      (node (ref "U4") (pin "1") (pinfunction "AC_N_1") (pintype "passive"))
      (node (ref "XP4") (pin "3") (pinfunction "3_3") (pintype "passive"))
      (node (ref "XP5") (pin "1") (pinfunction "1_1") (pintype "passive"))
    )
    (net (code "5") (name "/ADDR_LED") (class "Default")
      (node (ref "R18") (pin "1") (pinfunction "1_1") (pintype "passive"))
      (node (ref "X3") (pin "2") (pinfunction "2_2") (pintype "passive"))
    )
    (net (code "6") (name "/BLE_BCLK") (class "Default")
      (node (ref "R3") (pin "2") (pinfunction "2_2") (pintype "passive"))
      (node (ref "X2") (pin "7") (pinfunction "7_7") (pintype "passive"))
    )
    (net (code "7") (name "/BLE_LRCLK") (class "Default")
      (node (ref "R2") (pin "2") (pinfunction "2_2") (pintype "passive"))
      (node (ref "X2") (pin "5") (pinfunction "5_5") (pintype "passive"))
    )
    (net (code "8") (name "/BLE_SDATA") (class "Default")
      (node (ref "R1") (pin "2") (pinfunction "2_2") (pintype "passive"))
      (node (ref "X2") (pin "3") (pinfunction "3_3") (pintype "passive"))
    )
    (net (code "9") (name "/ENC_A") (class "Default")
      (node (ref "DD2") (pin "35") (pinfunction "IO42_35") (pintype "passive"))
      (node (ref "X1") (pin "3") (pinfunction "3_3") (pintype "passive"))
    )
    (net (code "10") (name "/ENC_B") (class "Default")
      (node (ref "DD2") (pin "34") (pinfunction "IO41_34") (pintype "passive"))
      (node (ref "X1") (pin "2") (pinfunction "2_2") (pintype "passive"))
    )
    (net (code "11") (name "/ESP32_BCLK") (class "Default")
      (node (ref "R26") (pin "2") (pinfunction "2_2") (pintype "passive"))
      (node (ref "X5") (pin "7") (pinfunction "7_7") (pintype "passive"))
    )
    (net (code "12") (name "/ESP32_DIN") (class "Default")
      (node (ref "R24") (pin "2") (pinfunction "2_2") (pintype "passive"))
      (node (ref "X5") (pin "3") (pinfunction "3_3") (pintype "passive"))
    )
    (net (code "13") (name "/ESP32_LRCLK") (class "Default")
      (node (ref "R25") (pin "2") (pinfunction "2_2") (pintype "passive"))
      (node (ref "X5") (pin "5") (pinfunction "5_5") (pintype "passive"))
    )
    (net (code "14") (name "/LCD_CS") (class "Default")
      (node (ref "DD2") (pin "29") (pinfunction "IO36_29") (pintype "passive"))
      (node (ref "X4") (pin "1") (pinfunction "1_1") (pintype "passive"))
    )
    (net (code "15") (name "/LCD_RS") (class "Default")
      (node (ref "DD2") (pin "30") (pinfunction "IO37_30") (pintype "passive"))
      (node (ref "X4") (pin "3") (pinfunction "3_3") (pintype "passive"))
    )
    (net (code "16") (name "/LCD_SCL") (class "Default")
      (node (ref "DD2") (pin "31") (pinfunction "IO38_31") (pintype "passive"))
      (node (ref "R15") (pin "1") (pinfunction "1_1") (pintype "passive"))
      (node (ref "X4") (pin "4") (pinfunction "4_4") (pintype "passive"))
    )
    (net (code "17") (name "/LCD_SDA") (class "Default")
      (node (ref "DD2") (pin "32") (pinfunction "IO39_32") (pintype "passive"))
      (node (ref "R19") (pin "1") (pinfunction "1_1") (pintype "passive"))
      (node (ref "X4") (pin "5") (pinfunction "5_5") (pintype "passive"))
    )
    (net (code "18") (name "/MCLK_") (class "Default")
      (node (ref "R4") (pin "2") (pinfunction "2_2") (pintype "passive"))
      (node (ref "X2") (pin "9") (pinfunction "9_9") (pintype "passive"))
    )
    (net (code "19") (name "/SCL_ISO") (class "Default")
      (node (ref "DD2") (pin "18") (pinfunction "IO10_18") (pintype "passive"))
      (node (ref "X5") (pin "12") (pinfunction "12_12") (pintype "passive"))
    )
    (net (code "20") (name "/SDA_ISO") (class "Default")
      (node (ref "DD2") (pin "17") (pinfunction "IO9_17") (pintype "passive"))
      (node (ref "X5") (pin "11") (pinfunction "11_11") (pintype "passive"))
    )
    (net (code "21") (name "/USB_P_N") (class "Default")
      (node (ref "DD2") (pin "13") (pinfunction "IO19_13") (pintype "passive"))
      (node (ref "VD4") (pin "6") (pinfunction "D+OUT_6") (pintype "passive"))
    )
    (net (code "22") (name "/USB_P_P") (class "Default")
      (node (ref "DD2") (pin "14") (pinfunction "IO20_14") (pintype "passive"))
      (node (ref "VD4") (pin "4") (pinfunction "D-OUT_4") (pintype "passive"))
    )
    (net (code "23") (name "/Vfb=0,6") (class "Default")
      (node (ref "R11") (pin "2") (pinfunction "2_2") (pintype "passive"))
      (node (ref "R12") (pin "2") (pinfunction "2_2") (pintype "passive"))
      (node (ref "R6") (pin "1") (pinfunction "1_1") (pintype "passive"))
      (node (ref "U5") (pin "3") (pinfunction "FB_3") (pintype "passive"))
    )
    (net (code "24") (name "/Vfb=0.6") (class "Default")
      (node (ref "R34") (pin "1") (pinfunction "1_1") (pintype "passive"))
      (node (ref "R37") (pin "2") (pinfunction "2_2") (pintype "passive"))
      (node (ref "U6") (pin "3") (pinfunction "FB_3") (pintype "passive"))
    )
    (net (code "25") (name "/cADAU_RES") (class "Default")
      (node (ref "R21") (pin "1") (pinfunction "1_1") (pintype "passive"))
      (node (ref "X2") (pin "13") (pinfunction "13_13") (pintype "passive"))
    )
    (net (code "26") (name "/cBLE_POW_EN") (class "Default")
      (node (ref "DD2") (pin "4") (pinfunction "IO4_4") (pintype "passive"))
      (node (ref "VT3") (pin "1") (pinfunction "B_1") (pintype "passive"))
    )
    (net (code "27") (name "/cBOOT") (class "Default")
      (node (ref "DD2") (pin "27") (pinfunction "IO0_27") (pintype "passive"))
      (node (ref "R28") (pin "2") (pinfunction "2_2") (pintype "passive"))
      (node (ref "SB1") (pin "1") (pinfunction "1_1") (pintype "passive"))
    )
    (net (code "28") (name "/cEN_ADDR_LED") (class "Default")
      (node (ref "DD2") (pin "21") (pinfunction "IO13_21") (pintype "passive"))
      (node (ref "VT6") (pin "1") (pinfunction "B_1") (pintype "passive"))
    )
    (net (code "29") (name "/cEN_POW_ADAU") (class "Default")
      (node (ref "R30") (pin "2") (pinfunction "2_2") (pintype "passive"))
      (node (ref "VD1") (pin "1") (pinfunction "VIN_1") (pintype "passive"))
    )
    (net (code "30") (name "/cLINE_SW") (class "Default")
      (node (ref "R20") (pin "1") (pinfunction "1_1") (pintype "passive"))
      (node (ref "X2") (pin "12") (pinfunction "12_12") (pintype "passive"))
    )
    (net (code "31") (name "/cMCU_RES") (class "Default")
      (node (ref "C23") (pin "1") (pinfunction "1_1") (pintype "passive"))
      (node (ref "DD2") (pin "3") (pinfunction "EN_3") (pintype "passive"))
      (node (ref "R29") (pin "2") (pinfunction "2_2") (pintype "passive"))
      (node (ref "SB2") (pin "1") (pinfunction "1_1") (pintype "passive"))
    )
    (net (code "32") (name "/cMUTE") (class "Default")
      (node (ref "R22") (pin "1") (pinfunction "1_1") (pintype "passive"))
      (node (ref "X2") (pin "14") (pinfunction "14_14") (pintype "passive"))
    )
    (net (code "33") (name "/cPWM_FAN1") (class "Default")
      (node (ref "DD2") (pin "24") (pinfunction "IO47_24") (pintype "passive"))
      (node (ref "R27") (pin "1") (pinfunction "1_1") (pintype "passive"))
    )
    (net (code "34") (name "/cPWM_FAN2") (class "Default")
      (node (ref "DD2") (pin "25") (pinfunction "IO48_25") (pintype "passive"))
      (node (ref "R31") (pin "1") (pinfunction "1_1") (pintype "passive"))
    )
    (net (code "35") (name "/cSYS_POW_EN") (class "Default")
      (node (ref "DD2") (pin "20") (pinfunction "IO12_20") (pintype "passive"))
      (node (ref "VT4") (pin "1") (pinfunction "B_1") (pintype "passive"))
    )
    (net (code "36") (name "/xBUTTON") (class "Default")
      (node (ref "DD2") (pin "38") (pinfunction "IO2_38") (pintype "passive"))
      (node (ref "X1") (pin "4") (pinfunction "4_4") (pintype "passive"))
    )
    (net (code "37") (name "3V3BLE") (class "Default")
      (node (ref "DD1") (pin "7") (pinfunction "BAT_SENSE_7") (pintype "passive"))
      (node (ref "FB1") (pin "1") (pintype "passive"))
      (node (ref "FB2") (pin "1") (pintype "passive"))
      (node (ref "VT1") (pin "D") (pinfunction "D_D") (pintype "passive"))
    )
    (net (code "38") (name "3V3_ISO") (class "Default")
      (node (ref "C25") (pin "1") (pinfunction "1_1") (pintype "passive"))
      (node (ref "C7") (pin "1") (pinfunction "1_1") (pintype "passive"))
      (node (ref "FB3") (pin "2") (pintype "passive"))
      (node (ref "R15") (pin "2") (pinfunction "2_2") (pintype "passive"))
      (node (ref "R19") (pin "2") (pinfunction "2_2") (pintype "passive"))
      (node (ref "R23") (pin "2") (pinfunction "2_2") (pintype "passive"))
      (node (ref "R28") (pin "1") (pinfunction "1_1") (pintype "passive"))
      (node (ref "R29") (pin "1") (pinfunction "1_1") (pintype "passive"))
      (node (ref "R9") (pin "1") (pinfunction "1_1") (pintype "passive"))
      (node (ref "U7") (pin "2") (pinfunction "VOUT_2") (pintype "passive"))
      (node (ref "U7") (pin "4") (pinfunction "VOUT_4") (pintype "passive"))
      (node (ref "VD4") (pin "5") (pinfunction "VBUS_5") (pintype "passive"))
      (node (ref "VT1") (pin "S") (pinfunction "S_S") (pintype "passive"))
      (node (ref "X1") (pin "1") (pinfunction "1_1") (pintype "passive"))
      (node (ref "X4") (pin "2") (pinfunction "2_2") (pintype "passive"))
      (node (ref "X4") (pin "6") (pinfunction "6_6") (pintype "passive"))
      (node (ref "X5") (pin "13") (pinfunction "13_13") (pintype "passive"))
      (node (ref "X5") (pin "14") (pinfunction "14_14") (pintype "passive"))
      (node (ref "X6") (pin "3") (pinfunction "3_3") (pintype "passive"))
      (node (ref "X8") (pin "1") (pinfunction "1_1") (pintype "passive"))
    )
    (net (code "39") (name "5V0_ISO") (class "Default")
      (node (ref "C19") (pin "1") (pinfunction "1_1") (pintype "passive"))
      (node (ref "C22") (pin "1") (pinfunction "1_1") (pintype "passive"))
      (node (ref "R34") (pin "2") (pinfunction "2_2") (pintype "passive"))
      (node (ref "VD9") (pin "1") (pinfunction "K_1") (pintype "passive"))
      (node (ref "X3") (pin "1") (pinfunction "1_1") (pintype "passive"))
      (node (ref "X9") (pin "1") (pinfunction "1_1") (pintype "passive"))
    )
    (net (code "40") (name "12V0") (class "Default")
      (node (ref "C2") (pin "2") (pinfunction "2_2") (pintype "passive"))
      (node (ref "C3") (pin "1") (pinfunction "1_1") (pintype "passive"))
      (node (ref "U2") (pin "2") (pinfunction "VIN+_2") (pintype "passive"))
      (node (ref "VD1") (pin "3") (pinfunction "3_3") (pintype "passive"))
      (node (ref "XP2") (pin "1") (pinfunction "1_1") (pintype "passive"))
    )
    (net (code "41") (name "GND") (class "Default")
      (node (ref "C1") (pin "2") (pinfunction "2_2") (pintype "passive"))
      (node (ref "C2") (pin "1") (pinfunction "1_1") (pintype "passive"))
      (node (ref "C3") (pin "2") (pinfunction "2_2") (pintype "passive"))
      (node (ref "C4") (pin "2") (pinfunction "2_2") (pintype "passive"))
      (node (ref "U1") (pin "3") (pinfunction "VSS_3") (pintype "passive"))
      (node (ref "U2") (pin "1") (pinfunction "VIN-_1") (pintype "passive"))
      (node (ref "U2") (pin "4") (pinfunction "VOUT+_4") (pintype "passive"))
      (node (ref "XP2") (pin "2") (pinfunction "2_2") (pintype "passive"))
    )
    (net (code "42") (name "GND_ISO") (class "Default")
      (node (ref "C10") (pin "2") (pinfunction "2_2") (pintype "passive"))
      (node (ref "C11") (pin "2") (pinfunction "2_2") (pintype "passive"))
      (node (ref "C12") (pin "2") (pinfunction "2_2") (pintype "passive"))
      (node (ref "C13") (pin "2") (pinfunction "2_2") (pintype "passive"))
      (node (ref "C14") (pin "2") (pinfunction "2_2") (pintype "passive"))
      (node (ref "C15") (pin "1") (pinfunction "1_1") (pintype "passive"))
      (node (ref "C16") (pin "1") (pinfunction "1_1") (pintype "passive"))
      (node (ref "C17") (pin "1") (pinfunction "1_1") (pintype "passive"))
      (node (ref "C18") (pin "1") (pinfunction "1_1") (pintype "passive"))
      (node (ref "C19") (pin "2") (pinfunction "2_2") (pintype "passive"))
      (node (ref "C20") (pin "2") (pinfunction "2_2") (pintype "passive"))
      (node (ref "C21") (pin "2") (pinfunction "2_2") (pintype "passive"))
      (node (ref "C22") (pin "2") (pinfunction "2_2") (pintype "passive"))
      (node (ref "C23") (pin "2") (pinfunction "2_2") (pintype "passive"))
      (node (ref "C24") (pin "2") (pinfunction "2_2") (pintype "passive"))
      (node (ref "C25") (pin "2") (pinfunction "2_2") (pintype "passive"))
      (node (ref "C6") (pin "2") (pinfunction "2_2") (pintype "passive"))
      (node (ref "C7") (pin "2") (pinfunction "2_2") (pintype "passive"))
      (node (ref "C8") (pin "1") (pinfunction "1_1") (pintype "passive"))
      (node (ref "C9") (pin "1") (pinfunction "1_1") (pintype "passive"))
      (node (ref "DD1") (pin "1") (pinfunction "NC_1") (pintype "passive"))
      (node (ref "DD1") (pin "15") (pinfunction "GND_15") (pintype "passive"))
      (node (ref "DD1") (pin "21") (pinfunction "GND_21") (pintype "passive"))
      (node (ref "DD1") (pin "33") (pinfunction "NC_33") (pintype "passive"))
      (node (ref "DD1") (pin "38") (pinfunction "GND_38") (pintype "passive"))
      (node (ref "DD1") (pin "44") (pinfunction "GND_44") (pintype "passive"))
      (node (ref "DD1") (pin "45") (pinfunction "GND_45") (pintype "passive"))
      (node (ref "DD1") (pin "47") (pinfunction "GND_47") (pintype "passive"))
      (node (ref "DD2") (pin "1") (pinfunction "GND_1") (pintype "passive"))
      (node (ref "DD2") (pin "40") (pinfunction "GND_40") (pintype "passive"))
      (node (ref "DD2") (pin "TP") (pinfunction "GND_TP") (pintype "passive"))
      (node (ref "K1") (pin "1") (pintype "passive"))
      (node (ref "R11") (pin "1") (pinfunction "1_1") (pintype "passive"))
      (node (ref "R12") (pin "1") (pinfunction "1_1") (pintype "passive"))
      (node (ref "R16") (pin "1") (pinfunction "1_1") (pintype "passive"))
      (node (ref "R17") (pin "1") (pinfunction "1_1") (pintype "passive"))
      (node (ref "R37") (pin "1") (pinfunction "1_1") (pintype "passive"))
      (node (ref "SB1") (pin "2") (pinfunction "2_2") (pintype "passive"))
      (node (ref "SB2") (pin "2") (pinfunction "2_2") (pintype "passive"))
      (node (ref "U4") (pin "3") (pinfunction "VSS_3") (pintype "passive"))
      (node (ref "U5") (pin "2") (pinfunction "GND_2") (pintype "power_in"))
      (node (ref "U6") (pin "2") (pinfunction "GND_2") (pintype "power_in"))
      (node (ref "U7") (pin "1") (pinfunction "ADJ/GND_1") (pintype "passive"))
      (node (ref "VD1") (pin "2") (pinfunction "GND_2") (pintype "passive"))
      (node (ref "VD3") (pin "2") (pinfunction "A_2") (pintype "passive"))
      (node (ref "VD4") (pin "2") (pinfunction "GND_2") (pintype "passive"))
      (node (ref "VD6") (pin "2") (pinfunction "GND_2") (pintype "passive"))
      (node (ref "VD8") (pin "2") (pinfunction "GND_2") (pintype "passive"))
      (node (ref "VT3") (pin "2") (pinfunction "E_2") (pintype "passive"))
      (node (ref "VT4") (pin "2") (pinfunction "E_2") (pintype "passive"))
      (node (ref "VT6") (pin "2") (pinfunction "E_2") (pintype "passive"))
      (node (ref "X1") (pin "5") (pinfunction "5_5") (pintype "passive"))
      (node (ref "X1") (pin "MP") (pinfunction "MountPad_MP") (pintype "passive"))
      (node (ref "X11") (pin "MP") (pinfunction "MountPad_MP") (pintype "passive"))
      (node (ref "X2") (pin "1") (pinfunction "1_1") (pintype "passive"))
      (node (ref "X2") (pin "10") (pinfunction "10_10") (pintype "passive"))
      (node (ref "X2") (pin "11") (pinfunction "11_11") (pintype "passive"))
      (node (ref "X2") (pin "15") (pinfunction "15_15") (pintype "passive"))
      (node (ref "X2") (pin "2") (pinfunction "2_2") (pintype "passive"))
      (node (ref "X2") (pin "4") (pinfunction "4_4") (pintype "passive"))
      (node (ref "X2") (pin "6") (pinfunction "6_6") (pintype "passive"))
      (node (ref "X2") (pin "8") (pinfunction "8_8") (pintype "passive"))
      (node (ref "X3") (pin "3") (pinfunction "3_3") (pintype "passive"))
      (node (ref "X3") (pin "MP") (pinfunction "MountPad_MP") (pintype "passive"))
      (node (ref "X4") (pin "15") (pinfunction "15_15") (pintype "passive"))
      (node (ref "X4") (pin "7") (pinfunction "7_7") (pintype "passive"))
      (node (ref "X5") (pin "1") (pinfunction "1_1") (pintype "passive"))
      (node (ref "X5") (pin "10") (pinfunction "10_10") (pintype "passive"))
      (node (ref "X5") (pin "15") (pinfunction "15_15") (pintype "passive"))
      (node (ref "X5") (pin "2") (pinfunction "2_2") (pintype "passive"))
      (node (ref "X5") (pin "4") (pinfunction "4_4") (pintype "passive"))
      (node (ref "X5") (pin "6") (pinfunction "6_6") (pintype "passive"))
      (node (ref "X5") (pin "8") (pinfunction "8_8") (pintype "passive"))
      (node (ref "X5") (pin "9") (pinfunction "9_9") (pintype "passive"))
      (node (ref "X6") (pin "1") (pinfunction "1_1") (pintype "passive"))
      (node (ref "X6") (pin "MP") (pinfunction "MountPad_MP") (pintype "passive"))
      (node (ref "X7") (pin "MP") (pinfunction "MountPad_MP") (pintype "passive"))
      (node (ref "XP1") (pin "2") (pinfunction "2_2") (pintype "passive"))
      (node (ref "XP1") (pin "3") (pinfunction "3_3") (pintype "passive"))
      (node (ref "XP3") (pin "1") (pinfunction "GND_1") (pintype "passive"))
      (node (ref "XP3") (pin "12") (pinfunction "GND_12") (pintype "passive"))
    )
    (net (code "43") (name "LCD_GND") (class "Default")
      (node (ref "C5") (pin "2") (pinfunction "2_2") (pintype "passive"))
      (node (ref "U3") (pin "3") (pinfunction "VSS_3") (pintype "passive"))
      (node (ref "VD6") (pin "3") (pinfunction "3_3") (pintype "passive"))
      (node (ref "VD8") (pin "3") (pinfunction "3_3") (pintype "passive"))
      (node (ref "XS1") (pin "2") (pinfunction "2_2") (pintype "passive"))
      (node (ref "XS1") (pin "3") (pinfunction "3_3") (pintype "passive"))
    )
    (net (code "44") (name "Net-(DD1-BT_RF)") (class "Default")
      (node (ref "DD1") (pin "46") (pinfunction "BT_RF_46") (pintype "passive"))
      (node (ref "XP1") (pin "1") (pinfunction "1_1") (pintype "passive"))
    )
    (net (code "45") (name "Net-(DD1-GPIO15{slash}I2S_MCK)") (class "Default")
      (node (ref "DD1") (pin "6") (pinfunction "GPIO15/I2S_MCK_6") (pintype "passive"))
      (node (ref "R4") (pin "1") (pinfunction "1_1") (pintype "passive"))
    )
    (net (code "46") (name "Net-(DD1-GPIO16{slash}I2S_BCK)") (class "Default")
      (node (ref "DD1") (pin "5") (pinfunction "GPIO16/I2S_BCK_5") (pintype "passive"))
      (node (ref "R3") (pin "1") (pinfunction "1_1") (pintype "passive"))
    )
    (net (code "47") (name "Net-(DD1-PIO17{slash}I2S_LRCK)") (class "Default")
      (node (ref "DD1") (pin "4") (pinfunction "PIO17/I2S_LRCK_4") (pintype "passive"))
      (node (ref "R2") (pin "1") (pinfunction "1_1") (pintype "passive"))
    )
    (net (code "48") (name "Net-(DD1-PIO18{slash}I2S_DOUT)") (class "Default")
      (node (ref "DD1") (pin "3") (pinfunction "PIO18/I2S_DOUT_3") (pintype "passive"))
      (node (ref "R1") (pin "1") (pinfunction "1_1") (pintype "passive"))
    )
    (net (code "49") (name "Net-(DD1-SYS_CTRL)") (class "Default")
      (node (ref "DD1") (pin "13") (pinfunction "SYS_CTRL_13") (pintype "passive"))
      (node (ref "R5") (pin "2") (pinfunction "2_2") (pintype "passive"))
    )
    (net (code "50") (name "Net-(DD1-VBAT)") (class "Default")
      (node (ref "C8") (pin "2") (pinfunction "2_2") (pintype "passive"))
      (node (ref "C9") (pin "2") (pinfunction "2_2") (pintype "passive"))
      (node (ref "DD1") (pin "14") (pinfunction "VBAT_14") (pintype "passive"))
      (node (ref "FB1") (pin "2") (pintype "passive"))
      (node (ref "R5") (pin "1") (pinfunction "1_1") (pintype "passive"))
    )
    (net (code "51") (name "Net-(DD1-VDD_PADS1)") (class "Default")
      (node (ref "C14") (pin "1") (pinfunction "1_1") (pintype "passive"))
      (node (ref "C15") (pin "2") (pinfunction "2_2") (pintype "passive"))
      (node (ref "DD1") (pin "23") (pinfunction "VDD_PADS1_23") (pintype "passive"))
      (node (ref "DD1") (pin "24") (pinfunction "VDD_PADS3_7_24") (pintype "passive"))
      (node (ref "FB2") (pin "2") (pintype "passive"))
    )
    (net (code "52") (name "Net-(DD2-3V3)") (class "Default")
      (node (ref "C16") (pin "2") (pinfunction "2_2") (pintype "passive"))
      (node (ref "C17") (pin "2") (pinfunction "2_2") (pintype "passive"))
      (node (ref "C18") (pin "2") (pinfunction "2_2") (pintype "passive"))
      (node (ref "DD2") (pin "2") (pinfunction "3V3_2") (pintype "passive"))
      (node (ref "FB3") (pin "1") (pintype "passive"))
    )
    (net (code "53") (name "Net-(DD2-IO1)") (class "Default")
      (node (ref "DD2") (pin "39") (pinfunction "IO1_39") (pintype "passive"))
      (node (ref "R18") (pin "2") (pinfunction "2_2") (pintype "passive"))
    )
    (net (code "54") (name "Net-(DD2-IO5)") (class "Default")
      (node (ref "DD2") (pin "5") (pinfunction "IO5_5") (pintype "passive"))
      (node (ref "R20") (pin "2") (pinfunction "2_2") (pintype "passive"))
    )
    (net (code "55") (name "Net-(DD2-IO6)") (class "Default")
      (node (ref "DD2") (pin "6") (pinfunction "IO6_6") (pintype "passive"))
      (node (ref "R21") (pin "2") (pinfunction "2_2") (pintype "passive"))
    )
    (net (code "56") (name "Net-(DD2-IO7)") (class "Default")
      (node (ref "DD2") (pin "7") (pinfunction "IO7_7") (pintype "passive"))
      (node (ref "R22") (pin "2") (pinfunction "2_2") (pintype "passive"))
    )
    (net (code "57") (name "Net-(DD2-IO11)") (class "Default")
      (node (ref "DD2") (pin "19") (pinfunction "IO11_19") (pintype "passive"))
      (node (ref "R30") (pin "1") (pinfunction "1_1") (pintype "passive"))
    )
    (net (code "58") (name "Net-(DD2-IO16)") (class "Default")
      (node (ref "DD2") (pin "9") (pinfunction "IO16_9") (pintype "passive"))
      (node (ref "R24") (pin "1") (pinfunction "1_1") (pintype "passive"))
    )
    (net (code "59") (name "Net-(DD2-IO17)") (class "Default")
      (node (ref "DD2") (pin "10") (pinfunction "IO17_10") (pintype "passive"))
      (node (ref "R25") (pin "1") (pinfunction "1_1") (pintype "passive"))
    )
    (net (code "60") (name "Net-(DD2-IO18)") (class "Default")
      (node (ref "DD2") (pin "11") (pinfunction "IO18_11") (pintype "passive"))
      (node (ref "R26") (pin "1") (pinfunction "1_1") (pintype "passive"))
    )
    (net (code "61") (name "Net-(DD2-IO40)") (class "Default")
      (node (ref "DD2") (pin "33") (pinfunction "IO40_33") (pintype "passive"))
      (node (ref "R23") (pin "1") (pinfunction "1_1") (pintype "passive"))
      (node (ref "X6") (pin "2") (pinfunction "2_2") (pintype "passive"))
    )
    (net (code "62") (name "Net-(R7-Pad2)") (class "Default")
      (node (ref "R7") (pin "2") (pinfunction "2_2") (pintype "passive"))
      (node (ref "VT2") (pin "G") (pinfunction "G_G") (pintype "passive"))
    )
    (net (code "63") (name "Net-(R10-Pad2)") (class "Default")
      (node (ref "R10") (pin "2") (pinfunction "2_2") (pintype "passive"))
      (node (ref "VT1") (pin "G") (pinfunction "G_G") (pintype "passive"))
    )
    (net (code "64") (name "Net-(R35-Pad2)") (class "Default")
      (node (ref "R35") (pin "2") (pinfunction "2_2") (pintype "passive"))
      (node (ref "VT5") (pin "G") (pinfunction "G_G") (pintype "passive"))
    )
    (net (code "65") (name "Net-(U1-VDD)") (class "Default")
      (node (ref "C1") (pin "1") (pinfunction "1_1") (pintype "passive"))
      (node (ref "U1") (pin "4") (pinfunction "VDD_4") (pintype "passive"))
      (node (ref "VD1") (pin "4") (pinfunction "4_4") (pintype "passive"))
    )
    (net (code "66") (name "Net-(U5-EN)") (class "Default")
      (node (ref "C12") (pin "1") (pinfunction "1_1") (pintype "passive"))
      (node (ref "C13") (pin "1") (pinfunction "1_1") (pintype "passive"))
      (node (ref "L1") (pin "1") (pintype "passive"))
      (node (ref "U5") (pin "4") (pinfunction "EN_4") (pintype "passive"))
      (node (ref "U5") (pin "5") (pinfunction "IN_5") (pintype "passive"))
      (node (ref "VT2") (pin "D") (pinfunction "D_D") (pintype "passive"))
    )
    (net (code "67") (name "Net-(U5-SW)") (class "Default")
      (node (ref "L1") (pin "2") (pintype "passive"))
      (node (ref "U5") (pin "1") (pinfunction "SW_1") (pintype "power_in"))
      (node (ref "VD2") (pin "2") (pinfunction "A_2") (pintype "passive"))
    )
    (net (code "68") (name "Net-(U6-EN)") (class "Default")
      (node (ref "C20") (pin "1") (pinfunction "1_1") (pintype "passive"))
      (node (ref "C21") (pin "1") (pinfunction "1_1") (pintype "passive"))
      (node (ref "L2") (pin "1") (pintype "passive"))
      (node (ref "U6") (pin "4") (pinfunction "EN_4") (pintype "passive"))
      (node (ref "U6") (pin "5") (pinfunction "IN_5") (pintype "passive"))
      (node (ref "VT5") (pin "D") (pinfunction "D_D") (pintype "passive"))
      (node (ref "X10") (pin "2") (pinfunction "2_2") (pintype "passive"))
    )
    (net (code "69") (name "Net-(U6-SW)") (class "Default")
      (node (ref "L2") (pin "2") (pintype "passive"))
      (node (ref "U6") (pin "1") (pinfunction "SW_1") (pintype "power_in"))
      (node (ref "VD9") (pin "2") (pinfunction "A_2") (pintype "passive"))
    )
    (net (code "70") (name "Net-(VD2-K)") (class "Default")
      (node (ref "C10") (pin "1") (pinfunction "1_1") (pintype "passive"))
      (node (ref "C11") (pin "1") (pinfunction "1_1") (pintype "passive"))
      (node (ref "K1") (pin "2") (pintype "passive"))
      (node (ref "R6") (pin "2") (pinfunction "2_2") (pintype "passive"))
      (node (ref "VD2") (pin "1") (pinfunction "K_1") (pintype "passive"))
      (node (ref "VD3") (pin "1") (pinfunction "K_1") (pintype "passive"))
    )
    (net (code "71") (name "Net-(VD4-D+IN)") (class "Default")
      (node (ref "R13") (pin "2") (pinfunction "2_2") (pintype "passive"))
      (node (ref "VD4") (pin "1") (pinfunction "D+IN_1") (pintype "passive"))
    )
    (net (code "72") (name "Net-(VD4-D-IN)") (class "Default")
      (node (ref "R14") (pin "2") (pinfunction "2_2") (pintype "passive"))
      (node (ref "VD4") (pin "3") (pinfunction "D-IN_3") (pintype "passive"))
    )
    (net (code "73") (name "Net-(VD5-A)") (class "Default")
      (node (ref "VD5") (pin "2") (pinfunction "A_2") (pintype "passive"))
      (node (ref "VD6") (pin "4") (pinfunction "4_4") (pintype "passive"))
      (node (ref "X7") (pin "3") (pinfunction "3_3") (pintype "passive"))
    )
    (net (code "74") (name "Net-(VD6-VIN)") (class "Default")
      (node (ref "R27") (pin "2") (pinfunction "2_2") (pintype "passive"))
      (node (ref "VD6") (pin "1") (pinfunction "VIN_1") (pintype "passive"))
    )
    (net (code "75") (name "Net-(VD7-A)") (class "Default")
      (node (ref "VD7") (pin "2") (pinfunction "A_2") (pintype "passive"))
      (node (ref "VD8") (pin "4") (pinfunction "4_4") (pintype "passive"))
      (node (ref "X11") (pin "3") (pinfunction "3_3") (pintype "passive"))
    )
    (net (code "76") (name "Net-(VD8-VIN)") (class "Default")
      (node (ref "R31") (pin "2") (pinfunction "2_2") (pintype "passive"))
      (node (ref "VD8") (pin "1") (pinfunction "VIN_1") (pintype "passive"))
    )
    (net (code "77") (name "Net-(VT3-C)") (class "Default")
      (node (ref "R10") (pin "1") (pinfunction "1_1") (pintype "passive"))
      (node (ref "R9") (pin "2") (pinfunction "2_2") (pintype "passive"))
      (node (ref "VT3") (pin "3") (pinfunction "C_3") (pintype "passive"))
    )
    (net (code "78") (name "Net-(VT4-C)") (class "Default")
      (node (ref "R7") (pin "1") (pinfunction "1_1") (pintype "passive"))
      (node (ref "R8") (pin "1") (pinfunction "1_1") (pintype "passive"))
      (node (ref "VT4") (pin "3") (pinfunction "C_3") (pintype "passive"))
    )
    (net (code "79") (name "Net-(VT6-C)") (class "Default")
      (node (ref "R35") (pin "1") (pinfunction "1_1") (pintype "passive"))
      (node (ref "R36") (pin "1") (pinfunction "1_1") (pintype "passive"))
      (node (ref "VT6") (pin "3") (pinfunction "C_3") (pintype "passive"))
    )
    (net (code "80") (name "Net-(X10-Pad1)") (class "Default")
      (node (ref "X10") (pin "1") (pinfunction "1_1") (pintype "passive"))
      (node (ref "X9") (pin "2") (pinfunction "2_2") (pintype "passive"))
    )
    (net (code "81") (name "Net-(XP3-CC1)") (class "Default")
      (node (ref "R17") (pin "2") (pinfunction "2_2") (pintype "passive"))
      (node (ref "XP3") (pin "9") (pinfunction "CC1_9") (pintype "passive"))
    )
    (net (code "82") (name "Net-(XP3-CC2)") (class "Default")
      (node (ref "R16") (pin "2") (pinfunction "2_2") (pintype "passive"))
      (node (ref "XP3") (pin "3") (pinfunction "CC2_3") (pintype "passive"))
    )
    (net (code "83") (name "Net-(XP3-DN1)") (class "Default")
      (node (ref "R13") (pin "1") (pinfunction "1_1") (pintype "passive"))
      (node (ref "XP3") (pin "6") (pinfunction "DN1_6") (pintype "passive"))
      (node (ref "XP3") (pin "8") (pinfunction "DN2_8") (pintype "passive"))
    )
    (net (code "84") (name "Net-(XP3-DP1)") (class "Default")
      (node (ref "R14") (pin "1") (pinfunction "1_1") (pintype "passive"))
      (node (ref "XP3") (pin "5") (pinfunction "DP2_5") (pintype "passive"))
      (node (ref "XP3") (pin "7") (pinfunction "DP1_7") (pintype "passive"))
    )
    (net (code "85") (name "Net-(XP4-Pad2)") (class "Default")
      (node (ref "XP4") (pin "2") (pinfunction "2_2") (pintype "passive"))
      (node (ref "XP5") (pin "2") (pinfunction "2_2") (pintype "passive"))
    )
    (net (code "86") (name "VIN_ISO") (class "Default")
      (node (ref "C24") (pin "1") (pinfunction "1_1") (pintype "passive"))
      (node (ref "C6") (pin "1") (pinfunction "1_1") (pintype "passive"))
      (node (ref "R36") (pin "2") (pinfunction "2_2") (pintype "passive"))
      (node (ref "R8") (pin "2") (pinfunction "2_2") (pintype "passive"))
      (node (ref "U4") (pin "4") (pinfunction "VDD_4") (pintype "passive"))
      (node (ref "U7") (pin "3") (pinfunction "VIN_3") (pintype "passive"))
      (node (ref "VT2") (pin "S") (pinfunction "S_S") (pintype "passive"))
      (node (ref "VT5") (pin "S") (pinfunction "S_S") (pintype "passive"))
      (node (ref "X8") (pin "2") (pinfunction "2_2") (pintype "passive"))
    )
    (net (code "87") (name "VLCD") (class "Default")
      (node (ref "C5") (pin "1") (pinfunction "1_1") (pintype "passive"))
      (node (ref "U3") (pin "4") (pinfunction "VDD_4") (pintype "passive"))
      (node (ref "VD5") (pin "1") (pinfunction "K_1") (pintype "passive"))
      (node (ref "VD7") (pin "1") (pinfunction "K_1") (pintype "passive"))
      (node (ref "X11") (pin "1") (pinfunction "1_1") (pintype "passive"))
      (node (ref "X7") (pin "1") (pinfunction "1_1") (pintype "passive"))
      (node (ref "XS1") (pin "1") (pinfunction "1_1") (pintype "passive"))
    )
    (net (code "88") (name "unconnected-(DD1-1V8-Pad22)") (class "Default")
      (node (ref "DD1") (pin "22") (pinfunction "1V8_22") (pintype "passive+no_connect"))
    )
    (net (code "89") (name "unconnected-(DD1-AUDIO_HPL_N{slash}SPKL_N-Pad36)") (class "Default")
      (node (ref "DD1") (pin "36") (pinfunction "AUDIO_HPL_N/SPKL_N_36") (pintype "passive+no_connect"))
    )
    (net (code "90") (name "unconnected-(DD1-AUDIO_HPL_P{slash}SPKL_P-Pad37)") (class "Default")
      (node (ref "DD1") (pin "37") (pinfunction "AUDIO_HPL_P/SPKL_P_37") (pintype "passive+no_connect"))
    )
    (net (code "91") (name "unconnected-(DD1-AUDIO_HPR_N{slash}SPKR_N-Pad34)") (class "Default")
      (node (ref "DD1") (pin "34") (pinfunction "AUDIO_HPR_N/SPKR_N_34") (pintype "passive+no_connect"))
    )
    (net (code "92") (name "unconnected-(DD1-AUDIO_HPR_P{slash}SPKR_P-Pad35)") (class "Default")
      (node (ref "DD1") (pin "35") (pinfunction "AUDIO_HPR_P/SPKR_P_35") (pintype "passive+no_connect"))
    )
    (net (code "93") (name "unconnected-(DD1-AUDIO_MIC1N{slash}LINEIN_L_N-Pad42)") (class "Default")
      (node (ref "DD1") (pin "42") (pinfunction "AUDIO_MIC1N/LINEIN_L_N_42") (pintype "passive+no_connect"))
    )
    (net (code "94") (name "unconnected-(DD1-AUDIO_MIC1P{slash}LINEIN_L_P-Pad43)") (class "Default")
      (node (ref "DD1") (pin "43") (pinfunction "AUDIO_MIC1P/LINEIN_L_P_43") (pintype "passive+no_connect"))
    )
    (net (code "95") (name "unconnected-(DD1-AUDIO_MIC2N{slash}LINEIN_R_N-Pad40)") (class "Default")
      (node (ref "DD1") (pin "40") (pinfunction "AUDIO_MIC2N/LINEIN_R_N_40") (pintype "passive+no_connect"))
    )
    (net (code "96") (name "unconnected-(DD1-AUDIO_MIC2P{slash}LINEIN_R_P-Pad41)") (class "Default")
      (node (ref "DD1") (pin "41") (pinfunction "AUDIO_MIC2P/LINEIN_R_P_41") (pintype "passive+no_connect"))
    )
    (net (code "97") (name "unconnected-(DD1-AUDIO_MIC_BIAS-Pad39)") (class "Default")
      (node (ref "DD1") (pin "39") (pinfunction "AUDIO_MIC_BIAS_39") (pintype "passive+no_connect"))
    )
    (net (code "98") (name "unconnected-(DD1-CHG_EXT-Pad12)") (class "Default")
      (node (ref "DD1") (pin "12") (pinfunction "CHG_EXT_12") (pintype "passive+no_connect"))
    )
    (net (code "99") (name "unconnected-(DD1-LED(0)-Pad16)") (class "Default")
      (node (ref "DD1") (pin "16") (pinfunction "LED(0)_16") (pintype "passive+no_connect"))
    )
    (net (code "100") (name "unconnected-(DD1-LED(1)-Pad17)") (class "Default")
      (node (ref "DD1") (pin "17") (pinfunction "LED(1)_17") (pintype "passive+no_connect"))
    )
    (net (code "101") (name "unconnected-(DD1-LED(2)-Pad18)") (class "Default")
      (node (ref "DD1") (pin "18") (pinfunction "LED(2)_18") (pintype "passive+no_connect"))
    )
    (net (code "102") (name "unconnected-(DD1-LED(4)-Pad19)") (class "Default")
      (node (ref "DD1") (pin "19") (pinfunction "LED(4)_19") (pintype "passive+no_connect"))
    )
    (net (code "103") (name "unconnected-(DD1-LED(5)-Pad20)") (class "Default")
      (node (ref "DD1") (pin "20") (pinfunction "LED(5)_20") (pintype "passive+no_connect"))
    )
    (net (code "104") (name "unconnected-(DD1-PIO1-Pad32)") (class "Default")
      (node (ref "DD1") (pin "32") (pinfunction "PIO1_32") (pintype "passive+no_connect"))
    )
    (net (code "105") (name "unconnected-(DD1-PIO2-Pad31)") (class "Default")
      (node (ref "DD1") (pin "31") (pinfunction "PIO2_31") (pintype "passive+no_connect"))
    )
    (net (code "106") (name "unconnected-(DD1-PIO3-Pad26)") (class "Default")
      (node (ref "DD1") (pin "26") (pinfunction "PIO3_26") (pintype "passive+no_connect"))
    )
    (net (code "107") (name "unconnected-(DD1-PIO4-Pad25)") (class "Default")
      (node (ref "DD1") (pin "25") (pinfunction "PIO4_25") (pintype "passive+no_connect"))
    )
    (net (code "108") (name "unconnected-(DD1-PIO5-Pad28)") (class "Default")
      (node (ref "DD1") (pin "28") (pinfunction "PIO5_28") (pintype "passive+no_connect"))
    )
    (net (code "109") (name "unconnected-(DD1-PIO6-Pad27)") (class "Default")
      (node (ref "DD1") (pin "27") (pinfunction "PIO6_27") (pintype "passive+no_connect"))
    )
    (net (code "110") (name "unconnected-(DD1-PIO7-Pad30)") (class "Default")
      (node (ref "DD1") (pin "30") (pinfunction "PIO7_30") (pintype "passive+no_connect"))
    )
    (net (code "111") (name "unconnected-(DD1-PIO8-Pad29)") (class "Default")
      (node (ref "DD1") (pin "29") (pinfunction "PIO8_29") (pintype "passive+no_connect"))
    )
    (net (code "112") (name "unconnected-(DD1-PIO19{slash}I2S_DIN-Pad2)") (class "Default")
      (node (ref "DD1") (pin "2") (pinfunction "PIO19/I2S_DIN_2") (pintype "passive+no_connect"))
    )
    (net (code "113") (name "unconnected-(DD1-PIO20-Pad54)") (class "Default")
      (node (ref "DD1") (pin "54") (pinfunction "PIO20_54") (pintype "passive+no_connect"))
    )
    (net (code "114") (name "unconnected-(DD1-PIO21-Pad53)") (class "Default")
      (node (ref "DD1") (pin "53") (pinfunction "PIO21_53") (pintype "passive+no_connect"))
    )
    (net (code "115") (name "unconnected-(DD1-PIO52-Pad50)") (class "Default")
      (node (ref "DD1") (pin "50") (pinfunction "PIO52_50") (pintype "passive+no_connect"))
    )
    (net (code "116") (name "unconnected-(DD1-PIO53-Pad49)") (class "Default")
      (node (ref "DD1") (pin "49") (pinfunction "PIO53_49") (pintype "passive+no_connect"))
    )
    (net (code "117") (name "unconnected-(DD1-PIO54-Pad48)") (class "Default")
      (node (ref "DD1") (pin "48") (pinfunction "PIO54_48") (pintype "passive+no_connect"))
    )
    (net (code "118") (name "unconnected-(DD1-PIO60-Pad51)") (class "Default")
      (node (ref "DD1") (pin "51") (pinfunction "PIO60_51") (pintype "passive+no_connect"))
    )
    (net (code "119") (name "unconnected-(DD1-PIO61-Pad52)") (class "Default")
      (node (ref "DD1") (pin "52") (pinfunction "PIO61_52") (pintype "passive+no_connect"))
    )
    (net (code "120") (name "unconnected-(DD1-USB_DN-Pad8)") (class "Default")
      (node (ref "DD1") (pin "8") (pinfunction "USB_DN_8") (pintype "passive+no_connect"))
    )
    (net (code "121") (name "unconnected-(DD1-USB_DP-Pad9)") (class "Default")
      (node (ref "DD1") (pin "9") (pinfunction "USB_DP_9") (pintype "passive+no_connect"))
    )
    (net (code "122") (name "unconnected-(DD1-YCHG-Pad10)") (class "Default")
      (node (ref "DD1") (pin "10") (pinfunction "YCHG_10") (pintype "passive+no_connect"))
    )
    (net (code "123") (name "unconnected-(DD1-YCHG_SENSE-Pad11)") (class "Default")
      (node (ref "DD1") (pin "11") (pinfunction "YCHG_SENSE_11") (pintype "passive+no_connect"))
    )
    (net (code "124") (name "unconnected-(DD2-IO3-Pad15)") (class "Default")
      (node (ref "DD2") (pin "15") (pinfunction "IO3_15") (pintype "passive+no_connect"))
    )
    (net (code "125") (name "unconnected-(DD2-IO8-Pad12)") (class "Default")
      (node (ref "DD2") (pin "12") (pinfunction "IO8_12") (pintype "passive+no_connect"))
    )
    (net (code "126") (name "unconnected-(DD2-IO14-Pad22)") (class "Default")
      (node (ref "DD2") (pin "22") (pinfunction "IO14_22") (pintype "passive"))
    )
    (net (code "127") (name "unconnected-(DD2-IO15-Pad8)") (class "Default")
      (node (ref "DD2") (pin "8") (pinfunction "IO15_8") (pintype "passive+no_connect"))
    )
    (net (code "128") (name "unconnected-(DD2-IO21-Pad23)") (class "Default")
      (node (ref "DD2") (pin "23") (pinfunction "IO21_23") (pintype "passive"))
    )
    (net (code "129") (name "unconnected-(DD2-IO35-Pad28)") (class "Default")
      (node (ref "DD2") (pin "28") (pinfunction "IO35_28") (pintype "passive+no_connect"))
    )
    (net (code "130") (name "unconnected-(DD2-IO45-Pad26)") (class "Default")
      (node (ref "DD2") (pin "26") (pinfunction "IO45_26") (pintype "passive+no_connect"))
    )
    (net (code "131") (name "unconnected-(DD2-IO46-Pad16)") (class "Default")
      (node (ref "DD2") (pin "16") (pinfunction "IO46_16") (pintype "passive+no_connect"))
    )
    (net (code "132") (name "unconnected-(DD2-RXD0-Pad36)") (class "Default")
      (node (ref "DD2") (pin "36") (pinfunction "RXD0_36") (pintype "passive+no_connect"))
    )
    (net (code "133") (name "unconnected-(DD2-TXD0-Pad37)") (class "Default")
      (node (ref "DD2") (pin "37") (pinfunction "TXD0_37") (pintype "passive+no_connect"))
    )
    (net (code "134") (name "unconnected-(K1-NC-Pad5)") (class "Default")
      (node (ref "K1") (pin "5") (pinfunction "NC_5") (pintype "passive+no_connect"))
    )
    (net (code "135") (name "unconnected-(U5-NC-Pad6)") (class "Default")
      (node (ref "U5") (pin "6") (pinfunction "NC_6") (pintype "passive+no_connect"))
    )
    (net (code "136") (name "unconnected-(U6-NC-Pad6)") (class "Default")
      (node (ref "U6") (pin "6") (pinfunction "NC_6") (pintype "passive+no_connect"))
    )
    (net (code "137") (name "unconnected-(X4-Pad8)") (class "Default")
      (node (ref "X4") (pin "8") (pinfunction "8_8") (pintype "passive+no_connect"))
    )
    (net (code "138") (name "unconnected-(X4-Pad9)") (class "Default")
      (node (ref "X4") (pin "9") (pinfunction "9_9") (pintype "passive+no_connect"))
    )
    (net (code "139") (name "unconnected-(X4-Pad10)") (class "Default")
      (node (ref "X4") (pin "10") (pinfunction "10_10") (pintype "passive+no_connect"))
    )
    (net (code "140") (name "unconnected-(X4-Pad11)") (class "Default")
      (node (ref "X4") (pin "11") (pinfunction "11_11") (pintype "passive+no_connect"))
    )
    (net (code "141") (name "unconnected-(X4-Pad12)") (class "Default")
      (node (ref "X4") (pin "12") (pinfunction "12_12") (pintype "passive+no_connect"))
    )
    (net (code "142") (name "unconnected-(X4-Pad13)") (class "Default")
      (node (ref "X4") (pin "13") (pinfunction "13_13") (pintype "passive+no_connect"))
    )
    (net (code "143") (name "unconnected-(X4-Pad14)") (class "Default")
      (node (ref "X4") (pin "14") (pinfunction "14_14") (pintype "passive+no_connect"))
    )
    (net (code "144") (name "unconnected-(X7-Pad2)") (class "Default")
      (node (ref "X7") (pin "2") (pinfunction "2_2") (pintype "passive+no_connect"))
    )
    (net (code "145") (name "unconnected-(X11-Pad2)") (class "Default")
      (node (ref "X11") (pin "2") (pinfunction "2_2") (pintype "passive+no_connect"))
    )
    (net (code "146") (name "unconnected-(XP3-CH-PadMS)") (class "Default")
      (node (ref "XP3") (pin "MS") (pinfunction "CH_MS") (pintype "passive+no_connect"))
    )
    (net (code "147") (name "unconnected-(XP3-SBU1-Pad4)") (class "Default")
      (node (ref "XP3") (pin "4") (pinfunction "SBU1_4") (pintype "passive+no_connect"))
    )
    (net (code "148") (name "unconnected-(XP3-SBU2-Pad10)") (class "Default")
      (node (ref "XP3") (pin "10") (pinfunction "SBU2_10") (pintype "passive+no_connect"))
    )
    (net (code "149") (name "unconnected-(XP3-VBUS-Pad2)") (class "Default")
      (node (ref "XP3") (pin "2") (pinfunction "VBUS_2") (pintype "passive+no_connect"))
    )
    (net (code "150") (name "unconnected-(XP3-VBUS-Pad11)") (class "Default")
      (node (ref "XP3") (pin "11") (pinfunction "VBUS_11") (pintype "passive+no_connect"))
    )
  )
)
